# 3__schdoc.net
KiCad netlist of a schematic drawn in Altium Designer
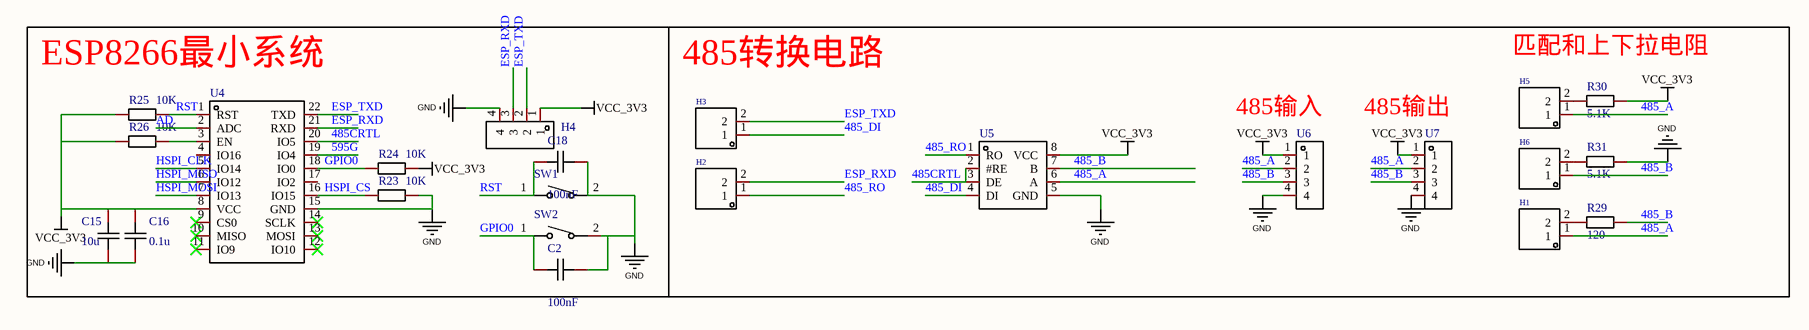
[diagram p0: 3_单片机最小系统.schdoc.schdoc]

(export (version "E")
  (design (tool "Eeschema 10.0.6"))
  (components
    (comp (ref "C2")
      (value "100nF")
      (fields (field (name "Comment") "CAP_0402"))
      (libsource (lib "altium-import") (part "root_0_CAP_0402_"))
    )
    (comp (ref "C15")
      (value "10u")
      (fields (field (name "Comment") "CAP_0402"))
      (libsource (lib "altium-import") (part "root_1_CAP_0402_"))
    )
    (comp (ref "C16")
      (value "0.1u")
      (fields (field (name "Comment") "CAP_0402"))
      (libsource (lib "altium-import") (part "root_1_CAP_0402_"))
    )
    (comp (ref "C18")
      (value "100nF")
      (fields (field (name "Comment") "CAP_0402"))
      (libsource (lib "altium-import") (part "root_0_CAP_0402_"))
    )
    (comp (ref "H1")
      (value "HDR-M_2.54_1x2P")
      (fields (field (name "MANUFACTURER") "Ckmtw(灿科盟)") (field (name "MANUFACTURER PART") "B-2100S02P-A110"))
      (libsource (lib "altium-import") (part "root_2_HDR-M_2.54_1x2P_"))
    )
    (comp (ref "H2")
      (value "HDR-M_2.54_1x2P")
      (fields (field (name "MANUFACTURER") "Ckmtw(灿科盟)") (field (name "MANUFACTURER PART") "B-2100S02P-A110"))
      (libsource (lib "altium-import") (part "root_2_HDR-M_2.54_1x2P_"))
    )
    (comp (ref "H3")
      (value "HDR-M_2.54_1x2P")
      (fields (field (name "MANUFACTURER") "Ckmtw(灿科盟)") (field (name "MANUFACTURER PART") "B-2100S02P-A110"))
      (libsource (lib "altium-import") (part "root_2_HDR-M_2.54_1x2P_"))
    )
    (comp (ref "H4")
      (value "HDR-M_2.54_1x4P")
      (fields (field (name "MANUFACTURER") "XFCN(兴飞)") (field (name "MANUFACTURER PART") "PZ254V-11-04P"))
      (libsource (lib "altium-import") (part "root_3_HDR-M_2.54_1x4P_"))
    )
    (comp (ref "H5")
      (value "HDR-M_2.54_1x2P")
      (fields (field (name "MANUFACTURER") "Ckmtw(灿科盟)") (field (name "MANUFACTURER PART") "B-2100S02P-A110"))
      (libsource (lib "altium-import") (part "root_2_HDR-M_2.54_1x2P_"))
    )
    (comp (ref "H6")
      (value "HDR-M_2.54_1x2P")
      (fields (field (name "MANUFACTURER") "Ckmtw(灿科盟)") (field (name "MANUFACTURER PART") "B-2100S02P-A110"))
      (libsource (lib "altium-import") (part "root_2_HDR-M_2.54_1x2P_"))
    )
    (comp (ref "R23")
      (value "10K")
      (fields (field (name "Comment") "Res_0402"))
      (libsource (lib "altium-import") (part "root_0_Res_0402_"))
    )
    (comp (ref "R24")
      (value "10K")
      (fields (field (name "Comment") "Res_0402"))
      (libsource (lib "altium-import") (part "root_0_Res_0402_"))
    )
    (comp (ref "R25")
      (value "10K")
      (fields (field (name "Comment") "Res_0402"))
      (libsource (lib "altium-import") (part "root_0_Res_0402_"))
    )
    (comp (ref "R26")
      (value "10K")
      (fields (field (name "Comment") "Res_0402"))
      (libsource (lib "altium-import") (part "root_0_Res_0402_"))
    )
    (comp (ref "R29")
      (value "120")
      (fields (field (name "Comment") "Res_0402"))
      (libsource (lib "altium-import") (part "root_0_Res_0402_"))
    )
    (comp (ref "R30")
      (value "5.1K")
      (fields (field (name "Comment") "Res_0402"))
      (libsource (lib "altium-import") (part "root_0_Res_0402_"))
    )
    (comp (ref "R31")
      (value "5.1K")
      (fields (field (name "Comment") "Res_0402"))
      (libsource (lib "altium-import") (part "root_0_Res_0402_"))
    )
    (comp (ref "SW1")
      (value "TS-KG88C-ACT25F")
      (fields (field (name "MANUFACTURER") "HANBO(汉博)"))
      (libsource (lib "altium-import") (part "root_0_TS-KG88C-ACT25F_"))
    )
    (comp (ref "SW2")
      (value "TS-KG88C-ACT25F")
      (fields (field (name "MANUFACTURER") "HANBO(汉博)"))
      (libsource (lib "altium-import") (part "root_0_TS-KG88C-ACT25F_"))
    )
    (comp (ref "U4")
      (value "SMDESP8266-12F")
      (libsource (lib "altium-import") (part "root_0_SMDESP8266-12F_"))
    )
    (comp (ref "U5")
      (value "MAX3485ESA")
      (description "类型:收发器;数据速率:12Mbps;驱动器/接收器:1/1;")
      (fields (field (name "MANUFACTURER") "UMW(友台半导体)"))
      (libsource (lib "altium-import") (part "root_0_MAX3485ESA_"))
    )
    (comp (ref "U6")
      (value "DB125-2.54-4P-GN-S")
      (fields (field (name "MANUFACTURER") "DORABO(地博电气)"))
      (libsource (lib "altium-import") (part "root_0_DB125-2.54-4P-GN-S_"))
    )
    (comp (ref "U7")
      (value "DB125-2.54-4P-GN-S")
      (fields (field (name "MANUFACTURER") "DORABO(地博电气)"))
      (libsource (lib "altium-import") (part "root_0_DB125-2.54-4P-GN-S_"))
    )
  )
  (nets
    (net (code "1") (name "/485CRTL") (class "Default")
      (node (ref "U4") (pin "20") (pinfunction "IO5_20") (pintype "passive"))
      (node (ref "U5") (pin "2") (pinfunction "#RE_2") (pintype "passive"))
      (node (ref "U5") (pin "3") (pinfunction "DE_3") (pintype "passive"))
    )
    (net (code "2") (name "/485_A") (class "Default")
      (node (ref "H1") (pin "1") (pinfunction "1_1") (pintype "passive"))
      (node (ref "H5") (pin "1") (pinfunction "1_1") (pintype "passive"))
      (node (ref "U5") (pin "6") (pinfunction "A_6") (pintype "passive"))
      (node (ref "U6") (pin "2") (pinfunction "2_2") (pintype "passive"))
      (node (ref "U7") (pin "2") (pinfunction "2_2") (pintype "passive"))
    )
    (net (code "3") (name "/485_B") (class "Default")
      (node (ref "H6") (pin "1") (pinfunction "1_1") (pintype "passive"))
      (node (ref "R29") (pin "2") (pinfunction "2_2") (pintype "passive"))
      (node (ref "U5") (pin "7") (pinfunction "B_7") (pintype "passive"))
      (node (ref "U6") (pin "3") (pinfunction "3_3") (pintype "passive"))
      (node (ref "U7") (pin "3") (pinfunction "3_3") (pintype "passive"))
    )
    (net (code "4") (name "/485_DI") (class "Default")
      (node (ref "H3") (pin "1") (pinfunction "1_1") (pintype "passive"))
      (node (ref "U5") (pin "4") (pinfunction "DI_4") (pintype "passive"))
    )
    (net (code "5") (name "/485_RO") (class "Default")
      (node (ref "H2") (pin "1") (pinfunction "1_1") (pintype "passive"))
      (node (ref "U5") (pin "1") (pinfunction "RO_1") (pintype "passive"))
    )
    (net (code "6") (name "/595G") (class "Default")
      (node (ref "U4") (pin "19") (pinfunction "IO4_19") (pintype "passive"))
    )
    (net (code "7") (name "/AD") (class "Default")
      (node (ref "U4") (pin "2") (pinfunction "ADC_2") (pintype "passive"))
    )
    (net (code "8") (name "/ESP_RXD") (class "Default")
      (node (ref "H2") (pin "2") (pinfunction "2_2") (pintype "passive"))
      (node (ref "H4") (pin "3") (pinfunction "3_3") (pintype "passive"))
      (node (ref "U4") (pin "21") (pinfunction "RXD_21") (pintype "passive"))
    )
    (net (code "9") (name "/ESP_TXD") (class "Default")
      (node (ref "H3") (pin "2") (pinfunction "2_2") (pintype "passive"))
      (node (ref "H4") (pin "2") (pinfunction "2_2") (pintype "passive"))
      (node (ref "U4") (pin "22") (pinfunction "TXD_22") (pintype "passive"))
    )
    (net (code "10") (name "/GPIO0") (class "Default")
      (node (ref "C2") (pin "1") (pinfunction "1_1") (pintype "passive"))
      (node (ref "R24") (pin "1") (pinfunction "1_1") (pintype "passive"))
      (node (ref "SW2") (pin "1") (pinfunction "1_1") (pintype "passive"))
      (node (ref "U4") (pin "18") (pinfunction "IO0_18") (pintype "passive"))
    )
    (net (code "11") (name "/HSPI_CLK") (class "Default")
      (node (ref "U4") (pin "5") (pinfunction "IO14_5") (pintype "passive"))
    )
    (net (code "12") (name "/HSPI_CS") (class "Default")
      (node (ref "R23") (pin "1") (pinfunction "1_1") (pintype "passive"))
      (node (ref "U4") (pin "16") (pinfunction "IO15_16") (pintype "passive"))
    )
    (net (code "13") (name "/HSPI_MISO") (class "Default")
      (node (ref "U4") (pin "6") (pinfunction "IO12_6") (pintype "passive"))
    )
    (net (code "14") (name "/HSPI_MOSI") (class "Default")
      (node (ref "U4") (pin "7") (pinfunction "IO13_7") (pintype "passive"))
    )
    (net (code "15") (name "/RST") (class "Default")
      (node (ref "C18") (pin "1") (pinfunction "1_1") (pintype "passive"))
      (node (ref "R25") (pin "2") (pinfunction "2_2") (pintype "passive"))
      (node (ref "SW1") (pin "1") (pinfunction "1_1") (pintype "passive"))
      (node (ref "U4") (pin "1") (pinfunction "RST_1") (pintype "passive"))
    )
    (net (code "16") (name "GND") (class "Default")
      (node (ref "C15") (pin "1") (pinfunction "1_1") (pintype "passive"))
      (node (ref "C16") (pin "1") (pinfunction "1_1") (pintype "passive"))
      (node (ref "C18") (pin "2") (pinfunction "2_2") (pintype "passive"))
      (node (ref "C2") (pin "2") (pinfunction "2_2") (pintype "passive"))
      (node (ref "H4") (pin "4") (pinfunction "4_4") (pintype "passive"))
      (node (ref "R23") (pin "2") (pinfunction "2_2") (pintype "passive"))
      (node (ref "R31") (pin "2") (pinfunction "2_2") (pintype "passive"))
      (node (ref "SW1") (pin "2") (pinfunction "2_2") (pintype "passive"))
      (node (ref "SW2") (pin "2") (pinfunction "2_2") (pintype "passive"))
      (node (ref "U4") (pin "15") (pinfunction "GND_15") (pintype "passive"))
      (node (ref "U5") (pin "5") (pinfunction "GND_5") (pintype "passive"))
      (node (ref "U6") (pin "4") (pinfunction "4_4") (pintype "passive"))
      (node (ref "U7") (pin "4") (pinfunction "4_4") (pintype "passive"))
    )
    (net (code "17") (name "Net-(H1-Pad2)") (class "Default")
      (node (ref "H1") (pin "2") (pinfunction "2_2") (pintype "passive"))
      (node (ref "R29") (pin "1") (pinfunction "1_1") (pintype "passive"))
    )
    (net (code "18") (name "Net-(H5-Pad2)") (class "Default")
      (node (ref "H5") (pin "2") (pinfunction "2_2") (pintype "passive"))
      (node (ref "R30") (pin "1") (pinfunction "1_1") (pintype "passive"))
    )
    (net (code "19") (name "Net-(H6-Pad2)") (class "Default")
      (node (ref "H6") (pin "2") (pinfunction "2_2") (pintype "passive"))
      (node (ref "R31") (pin "1") (pinfunction "1_1") (pintype "passive"))
    )
    (net (code "20") (name "Net-(U4-EN)") (class "Default")
      (node (ref "R26") (pin "2") (pinfunction "2_2") (pintype "passive"))
      (node (ref "U4") (pin "3") (pinfunction "EN_3") (pintype "passive"))
    )
    (net (code "21") (name "VCC_3V3") (class "Default")
      (node (ref "C15") (pin "2") (pinfunction "2_2") (pintype "passive"))
      (node (ref "C16") (pin "2") (pinfunction "2_2") (pintype "passive"))
      (node (ref "H4") (pin "1") (pinfunction "1_1") (pintype "passive"))
      (node (ref "R24") (pin "2") (pinfunction "2_2") (pintype "passive"))
      (node (ref "R25") (pin "1") (pinfunction "1_1") (pintype "passive"))
      (node (ref "R26") (pin "1") (pinfunction "1_1") (pintype "passive"))
      (node (ref "R30") (pin "2") (pinfunction "2_2") (pintype "passive"))
      (node (ref "U4") (pin "8") (pinfunction "VCC_8") (pintype "passive"))
      (node (ref "U5") (pin "8") (pinfunction "VCC_8") (pintype "passive"))
      (node (ref "U6") (pin "1") (pinfunction "1_1") (pintype "passive"))
      (node (ref "U7") (pin "1") (pinfunction "1_1") (pintype "passive"))
    )
    (net (code "22") (name "unconnected-(U4-CS0-Pad9)") (class "Default")
      (node (ref "U4") (pin "9") (pinfunction "CS0_9") (pintype "passive+no_connect"))
    )
    (net (code "23") (name "unconnected-(U4-IO2-Pad17)") (class "Default")
      (node (ref "U4") (pin "17") (pinfunction "IO2_17") (pintype "passive"))
    )
    (net (code "24") (name "unconnected-(U4-IO9-Pad11)") (class "Default")
      (node (ref "U4") (pin "11") (pinfunction "IO9_11") (pintype "passive+no_connect"))
    )
    (net (code "25") (name "unconnected-(U4-IO10-Pad12)") (class "Default")
      (node (ref "U4") (pin "12") (pinfunction "IO10_12") (pintype "passive+no_connect"))
    )
    (net (code "26") (name "unconnected-(U4-IO16-Pad4)") (class "Default")
      (node (ref "U4") (pin "4") (pinfunction "IO16_4") (pintype "passive"))
    )
    (net (code "27") (name "unconnected-(U4-MISO-Pad10)") (class "Default")
      (node (ref "U4") (pin "10") (pinfunction "MISO_10") (pintype "passive+no_connect"))
    )
    (net (code "28") (name "unconnected-(U4-MOSI-Pad13)") (class "Default")
      (node (ref "U4") (pin "13") (pinfunction "MOSI_13") (pintype "passive+no_connect"))
    )
    (net (code "29") (name "unconnected-(U4-SCLK-Pad14)") (class "Default")
      (node (ref "U4") (pin "14") (pinfunction "SCLK_14") (pintype "passive+no_connect"))
    )
  )
)
